# ModuleCarrier-EMW3166-v1_1_0.net
KiCad netlist of a schematic drawn in EAGLE
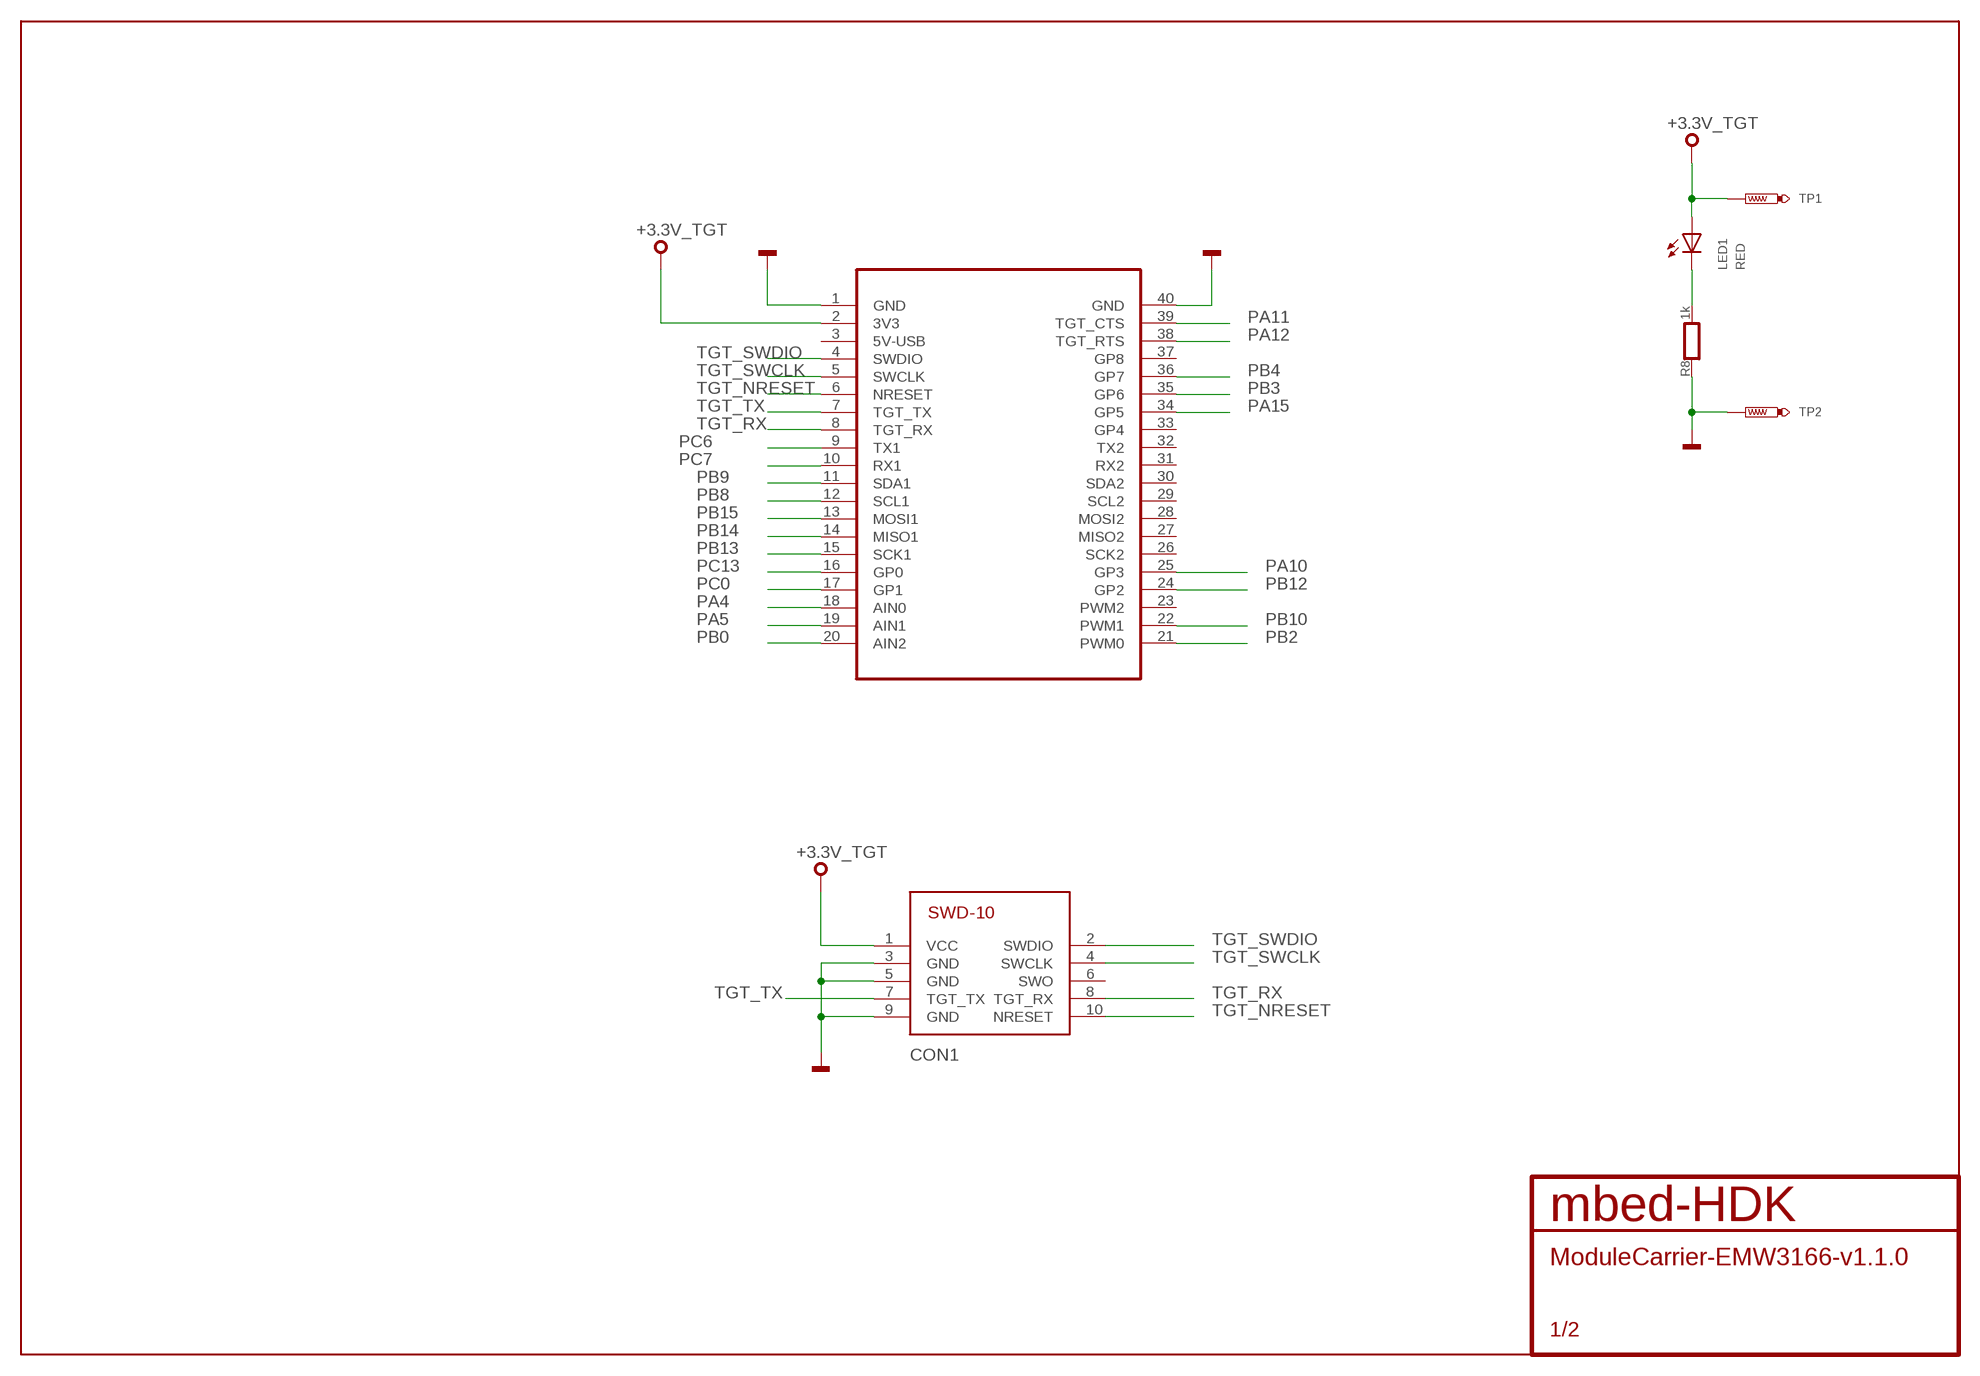
[diagram p0: schematic, sheet 1]
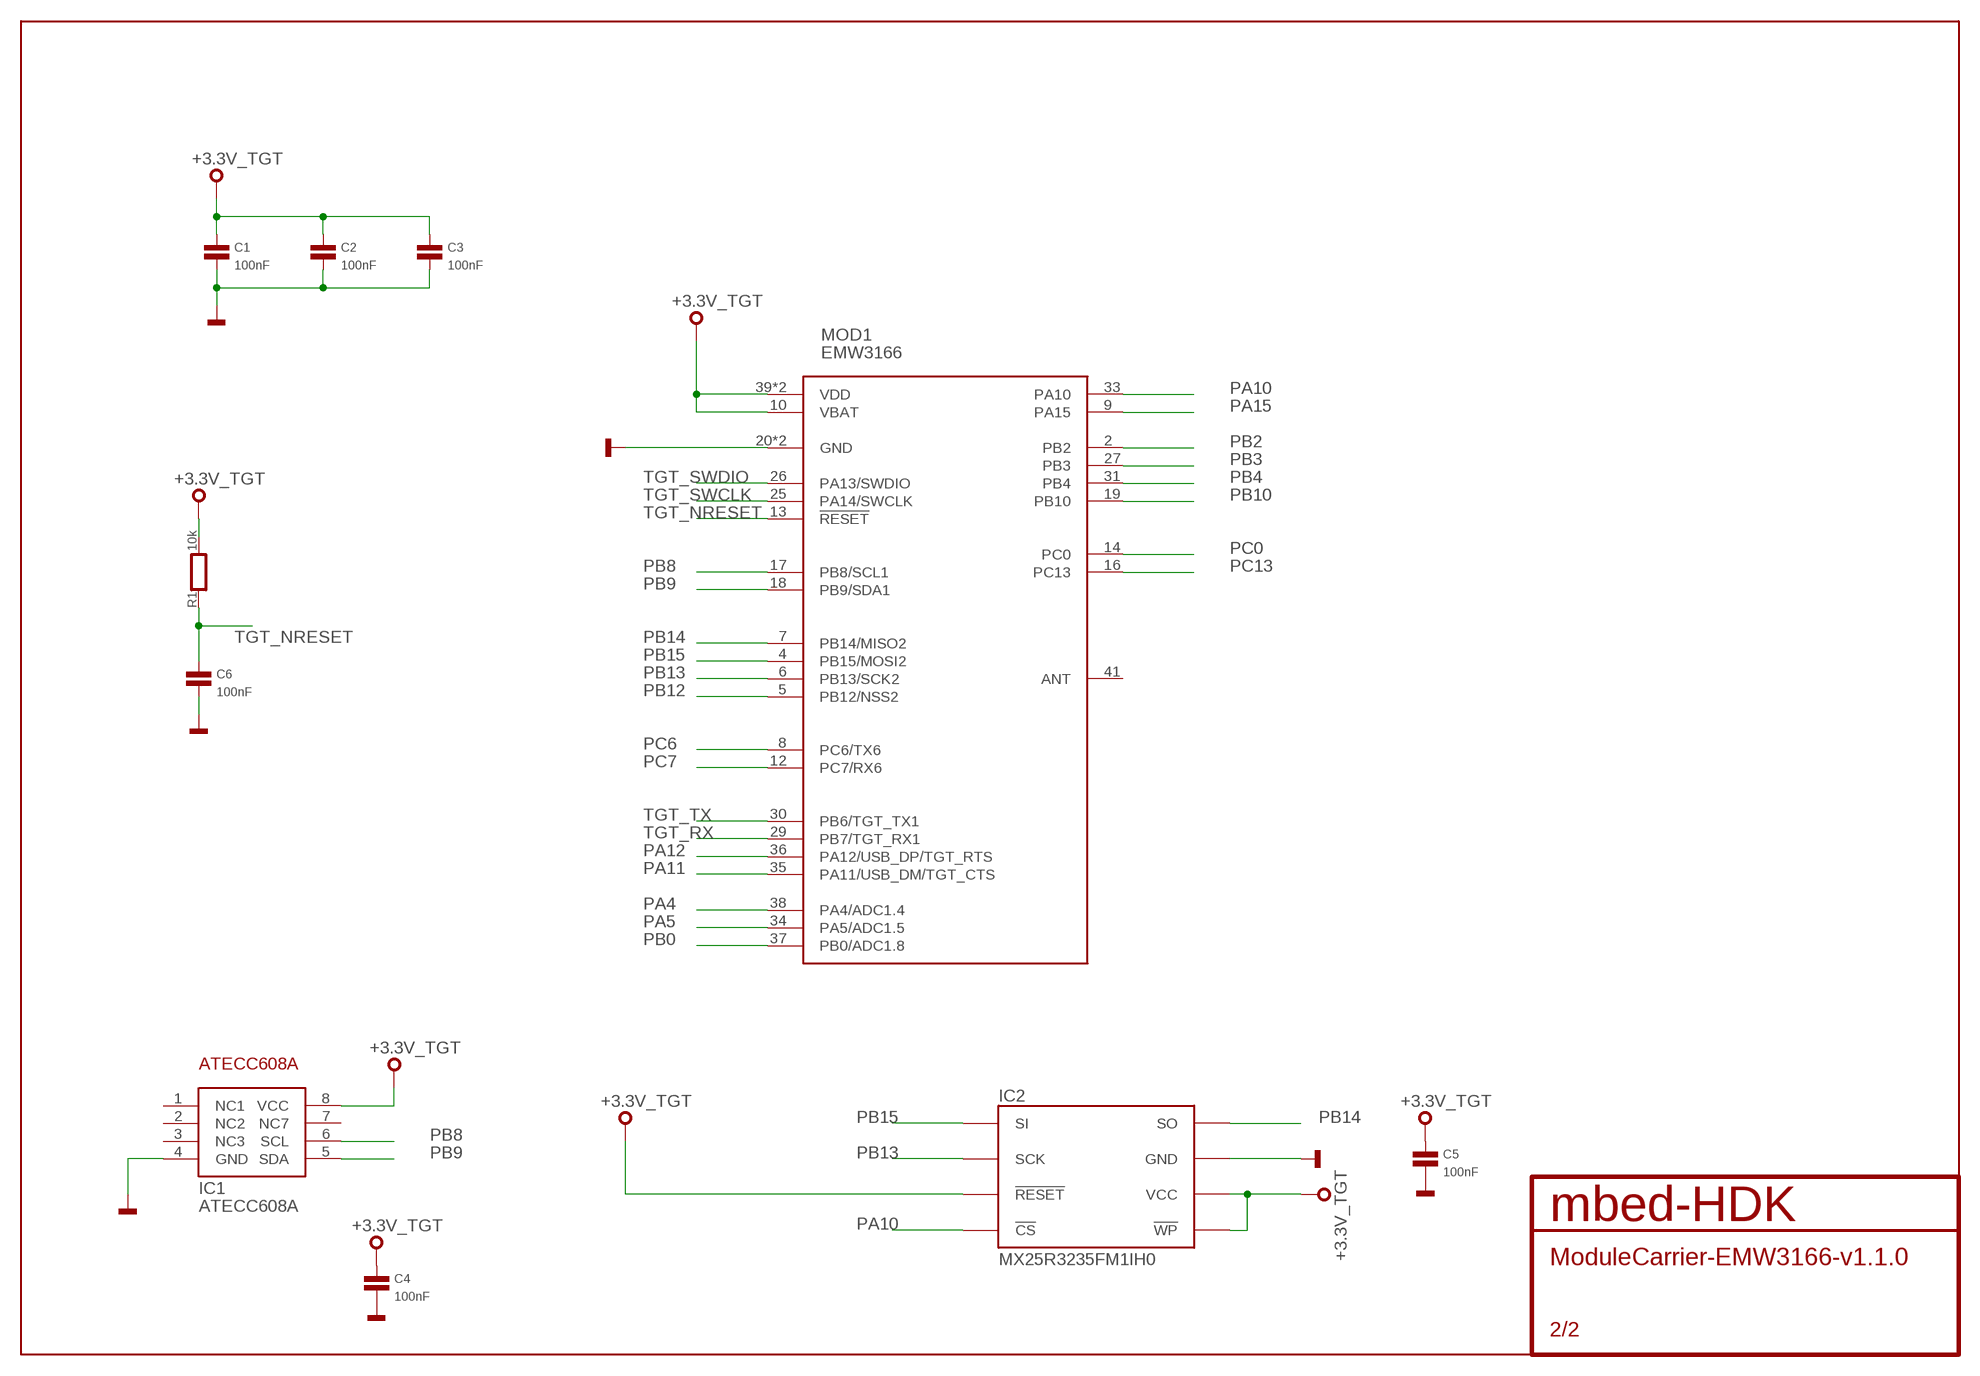
[diagram p1: schematic, sheet 2]

(export (version "E")
  (design (tool "Eeschema 10.0.6"))
  (components
    (comp (ref "CON1")
      (value "SWD-10/TC2050_SMD")
      (footprint "eagle-import:FTSH-105-02")
      (libsource (lib "eagle-import") (part "SWD-10/TC2050_SMD"))
    )
    (comp (ref "LED1")
      (value "RED")
      (footprint "eagle-import:CHIPLED_0603")
      (fields (field (name "MF") "Wurth Electronics Inc"))
      (libsource (lib "eagle-import") (part "SMD_LED0603"))
    )
    (comp (ref "R8")
      (value "1k")
      (footprint "eagle-import:0603")
      (libsource (lib "eagle-import") (part "RESISTOR0603"))
    )
    (comp (ref "TP1")
      (value "TEST-POINT-50R-PTH")
      (footprint "eagle-import:TP50-PTH")
      (libsource (lib "eagle-import") (part "TEST-POINT-50R-PTH"))
    )
    (comp (ref "TP2")
      (value "TEST-POINT-50R-PTH")
      (footprint "eagle-import:TP50-PTH")
      (libsource (lib "eagle-import") (part "TEST-POINT-50R-PTH"))
    )
    (comp (ref "U$1")
      (value "MODULE_DAUGHTER")
      (footprint "eagle-import:MODULE_DAUGHTER")
      (libsource (lib "eagle-import") (part "MODULE_DAUGHTER"))
    )
    (comp (ref "C1")
      (value "100nF")
      (footprint "eagle-import:0603")
      (libsource (lib "eagle-import") (part "CAPACITOR0603"))
    )
    (comp (ref "C2")
      (value "100nF")
      (footprint "eagle-import:0603")
      (libsource (lib "eagle-import") (part "CAPACITOR0603"))
    )
    (comp (ref "C3")
      (value "100nF")
      (footprint "eagle-import:0603")
      (libsource (lib "eagle-import") (part "CAPACITOR0603"))
    )
    (comp (ref "C4")
      (value "100nF")
      (footprint "eagle-import:0603")
      (libsource (lib "eagle-import") (part "CAPACITOR0603"))
    )
    (comp (ref "C5")
      (value "100nF")
      (footprint "eagle-import:0603")
      (libsource (lib "eagle-import") (part "CAPACITOR0603"))
    )
    (comp (ref "C6")
      (value "100nF")
      (footprint "eagle-import:0603")
      (libsource (lib "eagle-import") (part "CAPACITOR0603"))
    )
    (comp (ref "IC1")
      (value "ATECC608A")
      (footprint "eagle-import:SO8")
      (libsource (lib "eagle-import") (part "ATECC608A"))
    )
    (comp (ref "IC2")
      (value "MX25R3235FM1IH0")
      (footprint "eagle-import:SO8")
      (fields (field (name "MF") "Macronix"))
      (libsource (lib "eagle-import") (part "MX25R3235FM1IH0"))
    )
    (comp (ref "MOD1")
      (value "EMW3166")
      (footprint "eagle-import:EMW3166")
      (libsource (lib "eagle-import") (part "EMW3166"))
    )
    (comp (ref "R1")
      (value "10k")
      (footprint "eagle-import:0603")
      (libsource (lib "eagle-import") (part "RESISTOR0603"))
    )
  )
  (nets
    (net (code "1") (name "+3.3V_TGT") (class "Default")
      (node (ref "C1") (pin "1") (pinfunction "P$1_1") (pintype "passive"))
      (node (ref "C2") (pin "1") (pinfunction "P$1_1") (pintype "passive"))
      (node (ref "C3") (pin "1") (pinfunction "P$1_1") (pintype "passive"))
      (node (ref "C4") (pin "1") (pinfunction "P$1_1") (pintype "passive"))
      (node (ref "C5") (pin "1") (pinfunction "P$1_1") (pintype "passive"))
      (node (ref "CON1") (pin "1") (pinfunction "VCC_1") (pintype "bidirectional"))
      (node (ref "IC1") (pin "8") (pinfunction "VCC_8") (pintype "bidirectional"))
      (node (ref "IC2") (pin "3") (pinfunction "~{WP}_3") (pintype "bidirectional"))
      (node (ref "IC2") (pin "7") (pinfunction "~{RESET}_7") (pintype "bidirectional"))
      (node (ref "IC2") (pin "8") (pinfunction "VCC_8") (pintype "bidirectional"))
      (node (ref "LED1") (pin "A") (pinfunction "A_A") (pintype "passive"))
      (node (ref "MOD1") (pin "10") (pinfunction "VBAT_10") (pintype "bidirectional"))
      (node (ref "MOD1") (pin "39") (pinfunction "VDD_39") (pintype "bidirectional"))
      (node (ref "MOD1") (pin "40") (pinfunction "VDD_40") (pintype "bidirectional"))
      (node (ref "R1") (pin "2") (pinfunction "P$2_2") (pintype "passive"))
      (node (ref "TP1") (pin "TP") (pinfunction "TP_TP") (pintype "input"))
      (node (ref "U$1") (pin "2") (pinfunction "3V3_2") (pintype "bidirectional"))
    )
    (net (code "2") (name "GND") (class "Default")
      (node (ref "C1") (pin "2") (pinfunction "P$2_2") (pintype "passive"))
      (node (ref "C2") (pin "2") (pinfunction "P$2_2") (pintype "passive"))
      (node (ref "C3") (pin "2") (pinfunction "P$2_2") (pintype "passive"))
      (node (ref "C4") (pin "2") (pinfunction "P$2_2") (pintype "passive"))
      (node (ref "C5") (pin "2") (pinfunction "P$2_2") (pintype "passive"))
      (node (ref "C6") (pin "2") (pinfunction "P$2_2") (pintype "passive"))
      (node (ref "CON1") (pin "3") (pinfunction "GND_3") (pintype "bidirectional"))
      (node (ref "CON1") (pin "5") (pinfunction "GND_5") (pintype "bidirectional"))
      (node (ref "CON1") (pin "9") (pinfunction "GND_9") (pintype "bidirectional"))
      (node (ref "IC1") (pin "4") (pinfunction "GND_4") (pintype "bidirectional"))
      (node (ref "IC2") (pin "4") (pinfunction "GND_4") (pintype "bidirectional"))
      (node (ref "MOD1") (pin "20") (pinfunction "GND_20") (pintype "bidirectional"))
      (node (ref "MOD1") (pin "21") (pinfunction "GND_21") (pintype "bidirectional"))
      (node (ref "R8") (pin "1") (pinfunction "P$1_1") (pintype "passive"))
      (node (ref "TP2") (pin "TP") (pinfunction "TP_TP") (pintype "input"))
      (node (ref "U$1") (pin "1") (pinfunction "GND_1") (pintype "bidirectional"))
      (node (ref "U$1") (pin "40") (pinfunction "GND_40") (pintype "bidirectional"))
    )
    (net (code "3") (name "Net-(R8-P$2)") (class "Default")
      (node (ref "LED1") (pin "C") (pinfunction "C_C") (pintype "passive"))
      (node (ref "R8") (pin "2") (pinfunction "P$2_2") (pintype "passive"))
    )
    (net (code "4") (name "PA4") (class "Default")
      (node (ref "MOD1") (pin "38") (pinfunction "PA4/ADC1.4_38") (pintype "bidirectional"))
      (node (ref "U$1") (pin "18") (pinfunction "AIN0_18") (pintype "bidirectional"))
    )
    (net (code "5") (name "PA5") (class "Default")
      (node (ref "MOD1") (pin "34") (pinfunction "PA5/ADC1.5_34") (pintype "bidirectional"))
      (node (ref "U$1") (pin "19") (pinfunction "AIN1_19") (pintype "bidirectional"))
    )
    (net (code "6") (name "PA10") (class "Default")
      (node (ref "IC2") (pin "1") (pinfunction "~{CS}_1") (pintype "bidirectional"))
      (node (ref "MOD1") (pin "33") (pinfunction "PA10_33") (pintype "bidirectional"))
      (node (ref "U$1") (pin "25") (pinfunction "GP3_25") (pintype "bidirectional"))
    )
    (net (code "7") (name "PA11") (class "Default")
      (node (ref "MOD1") (pin "35") (pinfunction "PA11/USB_DM/TGT_CTS_35") (pintype "bidirectional"))
      (node (ref "U$1") (pin "39") (pinfunction "TGT_CTS_39") (pintype "bidirectional"))
    )
    (net (code "8") (name "PA12") (class "Default")
      (node (ref "MOD1") (pin "36") (pinfunction "PA12/USB_DP/TGT_RTS_36") (pintype "bidirectional"))
      (node (ref "U$1") (pin "38") (pinfunction "TGT_RTS_38") (pintype "bidirectional"))
    )
    (net (code "9") (name "PA15") (class "Default")
      (node (ref "MOD1") (pin "9") (pinfunction "PA15_9") (pintype "bidirectional"))
      (node (ref "U$1") (pin "34") (pinfunction "GP5_34") (pintype "bidirectional"))
    )
    (net (code "10") (name "PB0") (class "Default")
      (node (ref "MOD1") (pin "37") (pinfunction "PB0/ADC1.8_37") (pintype "bidirectional"))
      (node (ref "U$1") (pin "20") (pinfunction "AIN2_20") (pintype "bidirectional"))
    )
    (net (code "11") (name "PB2") (class "Default")
      (node (ref "MOD1") (pin "2") (pinfunction "PB2_2") (pintype "bidirectional"))
      (node (ref "U$1") (pin "21") (pinfunction "PWM0_21") (pintype "bidirectional"))
    )
    (net (code "12") (name "PB3") (class "Default")
      (node (ref "MOD1") (pin "27") (pinfunction "PB3_27") (pintype "bidirectional"))
      (node (ref "U$1") (pin "35") (pinfunction "GP6_35") (pintype "bidirectional"))
    )
    (net (code "13") (name "PB4") (class "Default")
      (node (ref "MOD1") (pin "31") (pinfunction "PB4_31") (pintype "bidirectional"))
      (node (ref "U$1") (pin "36") (pinfunction "GP7_36") (pintype "bidirectional"))
    )
    (net (code "14") (name "PB8") (class "Default")
      (node (ref "IC1") (pin "6") (pinfunction "SCL_6") (pintype "bidirectional"))
      (node (ref "MOD1") (pin "17") (pinfunction "PB8/SCL1_17") (pintype "bidirectional"))
      (node (ref "U$1") (pin "12") (pinfunction "SCL1_12") (pintype "bidirectional"))
    )
    (net (code "15") (name "PB9") (class "Default")
      (node (ref "IC1") (pin "5") (pinfunction "SDA_5") (pintype "bidirectional"))
      (node (ref "MOD1") (pin "18") (pinfunction "PB9/SDA1_18") (pintype "bidirectional"))
      (node (ref "U$1") (pin "11") (pinfunction "SDA1_11") (pintype "bidirectional"))
    )
    (net (code "16") (name "PB10") (class "Default")
      (node (ref "MOD1") (pin "19") (pinfunction "PB10_19") (pintype "bidirectional"))
      (node (ref "U$1") (pin "22") (pinfunction "PWM1_22") (pintype "bidirectional"))
    )
    (net (code "17") (name "PB12") (class "Default")
      (node (ref "MOD1") (pin "5") (pinfunction "PB12/NSS2_5") (pintype "bidirectional"))
      (node (ref "U$1") (pin "24") (pinfunction "GP2_24") (pintype "bidirectional"))
    )
    (net (code "18") (name "PB13") (class "Default")
      (node (ref "IC2") (pin "6") (pinfunction "SCK_6") (pintype "bidirectional"))
      (node (ref "MOD1") (pin "6") (pinfunction "PB13/SCK2_6") (pintype "bidirectional"))
      (node (ref "U$1") (pin "15") (pinfunction "SCK1_15") (pintype "bidirectional"))
    )
    (net (code "19") (name "PB14") (class "Default")
      (node (ref "IC2") (pin "2") (pinfunction "SO_2") (pintype "bidirectional"))
      (node (ref "MOD1") (pin "7") (pinfunction "PB14/MISO2_7") (pintype "bidirectional"))
      (node (ref "U$1") (pin "14") (pinfunction "MISO1_14") (pintype "bidirectional"))
    )
    (net (code "20") (name "PB15") (class "Default")
      (node (ref "IC2") (pin "5") (pinfunction "SI_5") (pintype "bidirectional"))
      (node (ref "MOD1") (pin "4") (pinfunction "PB15/MOSI2_4") (pintype "bidirectional"))
      (node (ref "U$1") (pin "13") (pinfunction "MOSI1_13") (pintype "bidirectional"))
    )
    (net (code "21") (name "PC0") (class "Default")
      (node (ref "MOD1") (pin "14") (pinfunction "PC0_14") (pintype "bidirectional"))
      (node (ref "U$1") (pin "17") (pinfunction "GP1_17") (pintype "bidirectional"))
    )
    (net (code "22") (name "PC6") (class "Default")
      (node (ref "MOD1") (pin "8") (pinfunction "PC6/TX6_8") (pintype "bidirectional"))
      (node (ref "U$1") (pin "9") (pinfunction "TX1_9") (pintype "bidirectional"))
    )
    (net (code "23") (name "PC7") (class "Default")
      (node (ref "MOD1") (pin "12") (pinfunction "PC7/RX6_12") (pintype "bidirectional"))
      (node (ref "U$1") (pin "10") (pinfunction "RX1_10") (pintype "bidirectional"))
    )
    (net (code "24") (name "PC13") (class "Default")
      (node (ref "MOD1") (pin "16") (pinfunction "PC13_16") (pintype "bidirectional"))
      (node (ref "U$1") (pin "16") (pinfunction "GP0_16") (pintype "bidirectional"))
    )
    (net (code "25") (name "TGT_NRESET") (class "Default")
      (node (ref "C6") (pin "1") (pinfunction "P$1_1") (pintype "passive"))
      (node (ref "CON1") (pin "10") (pinfunction "NRESET_10") (pintype "bidirectional"))
      (node (ref "MOD1") (pin "13") (pinfunction "~{RESET}_13") (pintype "bidirectional"))
      (node (ref "R1") (pin "1") (pinfunction "P$1_1") (pintype "passive"))
      (node (ref "U$1") (pin "6") (pinfunction "NRESET_6") (pintype "bidirectional"))
    )
    (net (code "26") (name "TGT_RX") (class "Default")
      (node (ref "CON1") (pin "8") (pinfunction "TGT_RX_8") (pintype "bidirectional"))
      (node (ref "MOD1") (pin "29") (pinfunction "PB7/TGT_RX1_29") (pintype "bidirectional"))
      (node (ref "U$1") (pin "8") (pinfunction "TGT_RX_8") (pintype "bidirectional"))
    )
    (net (code "27") (name "TGT_SWCLK") (class "Default")
      (node (ref "CON1") (pin "4") (pinfunction "SWCLK_4") (pintype "bidirectional"))
      (node (ref "MOD1") (pin "25") (pinfunction "PA14/SWCLK_25") (pintype "bidirectional"))
      (node (ref "U$1") (pin "5") (pinfunction "SWCLK_5") (pintype "bidirectional"))
    )
    (net (code "28") (name "TGT_SWDIO") (class "Default")
      (node (ref "CON1") (pin "2") (pinfunction "SWDIO_2") (pintype "bidirectional"))
      (node (ref "MOD1") (pin "26") (pinfunction "PA13/SWDIO_26") (pintype "bidirectional"))
      (node (ref "U$1") (pin "4") (pinfunction "SWDIO_4") (pintype "bidirectional"))
    )
    (net (code "29") (name "TGT_TX") (class "Default")
      (node (ref "CON1") (pin "7") (pinfunction "TGT_TX_7") (pintype "bidirectional"))
      (node (ref "MOD1") (pin "30") (pinfunction "PB6/TGT_TX1_30") (pintype "bidirectional"))
      (node (ref "U$1") (pin "7") (pinfunction "TGT_TX_7") (pintype "bidirectional"))
    )
    (net (code "30") (name "unconnected-(CON1-SWO-Pad6)") (class "Default")
      (node (ref "CON1") (pin "6") (pinfunction "SWO_6") (pintype "bidirectional"))
    )
    (net (code "31") (name "unconnected-(IC1-NC1-Pad1)") (class "Default")
      (node (ref "IC1") (pin "1") (pinfunction "NC1_1") (pintype "bidirectional"))
    )
    (net (code "32") (name "unconnected-(IC1-NC2-Pad2)") (class "Default")
      (node (ref "IC1") (pin "2") (pinfunction "NC2_2") (pintype "bidirectional"))
    )
    (net (code "33") (name "unconnected-(IC1-NC3-Pad3)") (class "Default")
      (node (ref "IC1") (pin "3") (pinfunction "NC3_3") (pintype "bidirectional"))
    )
    (net (code "34") (name "unconnected-(IC1-NC7-Pad7)") (class "Default")
      (node (ref "IC1") (pin "7") (pinfunction "NC7_7") (pintype "bidirectional"))
    )
    (net (code "35") (name "unconnected-(MOD1-ANT-Pad41)") (class "Default")
      (node (ref "MOD1") (pin "41") (pinfunction "ANT_41") (pintype "bidirectional"))
    )
    (net (code "36") (name "unconnected-(U$1-5V-USB-Pad3)") (class "Default")
      (node (ref "U$1") (pin "3") (pinfunction "5V-USB_3") (pintype "bidirectional"))
    )
    (net (code "37") (name "unconnected-(U$1-GP4-Pad33)") (class "Default")
      (node (ref "U$1") (pin "33") (pinfunction "GP4_33") (pintype "bidirectional"))
    )
    (net (code "38") (name "unconnected-(U$1-GP8-Pad37)") (class "Default")
      (node (ref "U$1") (pin "37") (pinfunction "GP8_37") (pintype "bidirectional"))
    )
    (net (code "39") (name "unconnected-(U$1-MISO2-Pad27)") (class "Default")
      (node (ref "U$1") (pin "27") (pinfunction "MISO2_27") (pintype "bidirectional"))
    )
    (net (code "40") (name "unconnected-(U$1-MOSI2-Pad28)") (class "Default")
      (node (ref "U$1") (pin "28") (pinfunction "MOSI2_28") (pintype "bidirectional"))
    )
    (net (code "41") (name "unconnected-(U$1-PWM2-Pad23)") (class "Default")
      (node (ref "U$1") (pin "23") (pinfunction "PWM2_23") (pintype "bidirectional"))
    )
    (net (code "42") (name "unconnected-(U$1-RX2-Pad31)") (class "Default")
      (node (ref "U$1") (pin "31") (pinfunction "RX2_31") (pintype "bidirectional"))
    )
    (net (code "43") (name "unconnected-(U$1-SCK2-Pad26)") (class "Default")
      (node (ref "U$1") (pin "26") (pinfunction "SCK2_26") (pintype "bidirectional"))
    )
    (net (code "44") (name "unconnected-(U$1-SCL2-Pad29)") (class "Default")
      (node (ref "U$1") (pin "29") (pinfunction "SCL2_29") (pintype "bidirectional"))
    )
    (net (code "45") (name "unconnected-(U$1-SDA2-Pad30)") (class "Default")
      (node (ref "U$1") (pin "30") (pinfunction "SDA2_30") (pintype "bidirectional"))
    )
    (net (code "46") (name "unconnected-(U$1-TX2-Pad32)") (class "Default")
      (node (ref "U$1") (pin "32") (pinfunction "TX2_32") (pintype "bidirectional"))
    )
  )
)
